# MCU.net
KiCad netlist of a schematic drawn in Altium Designer
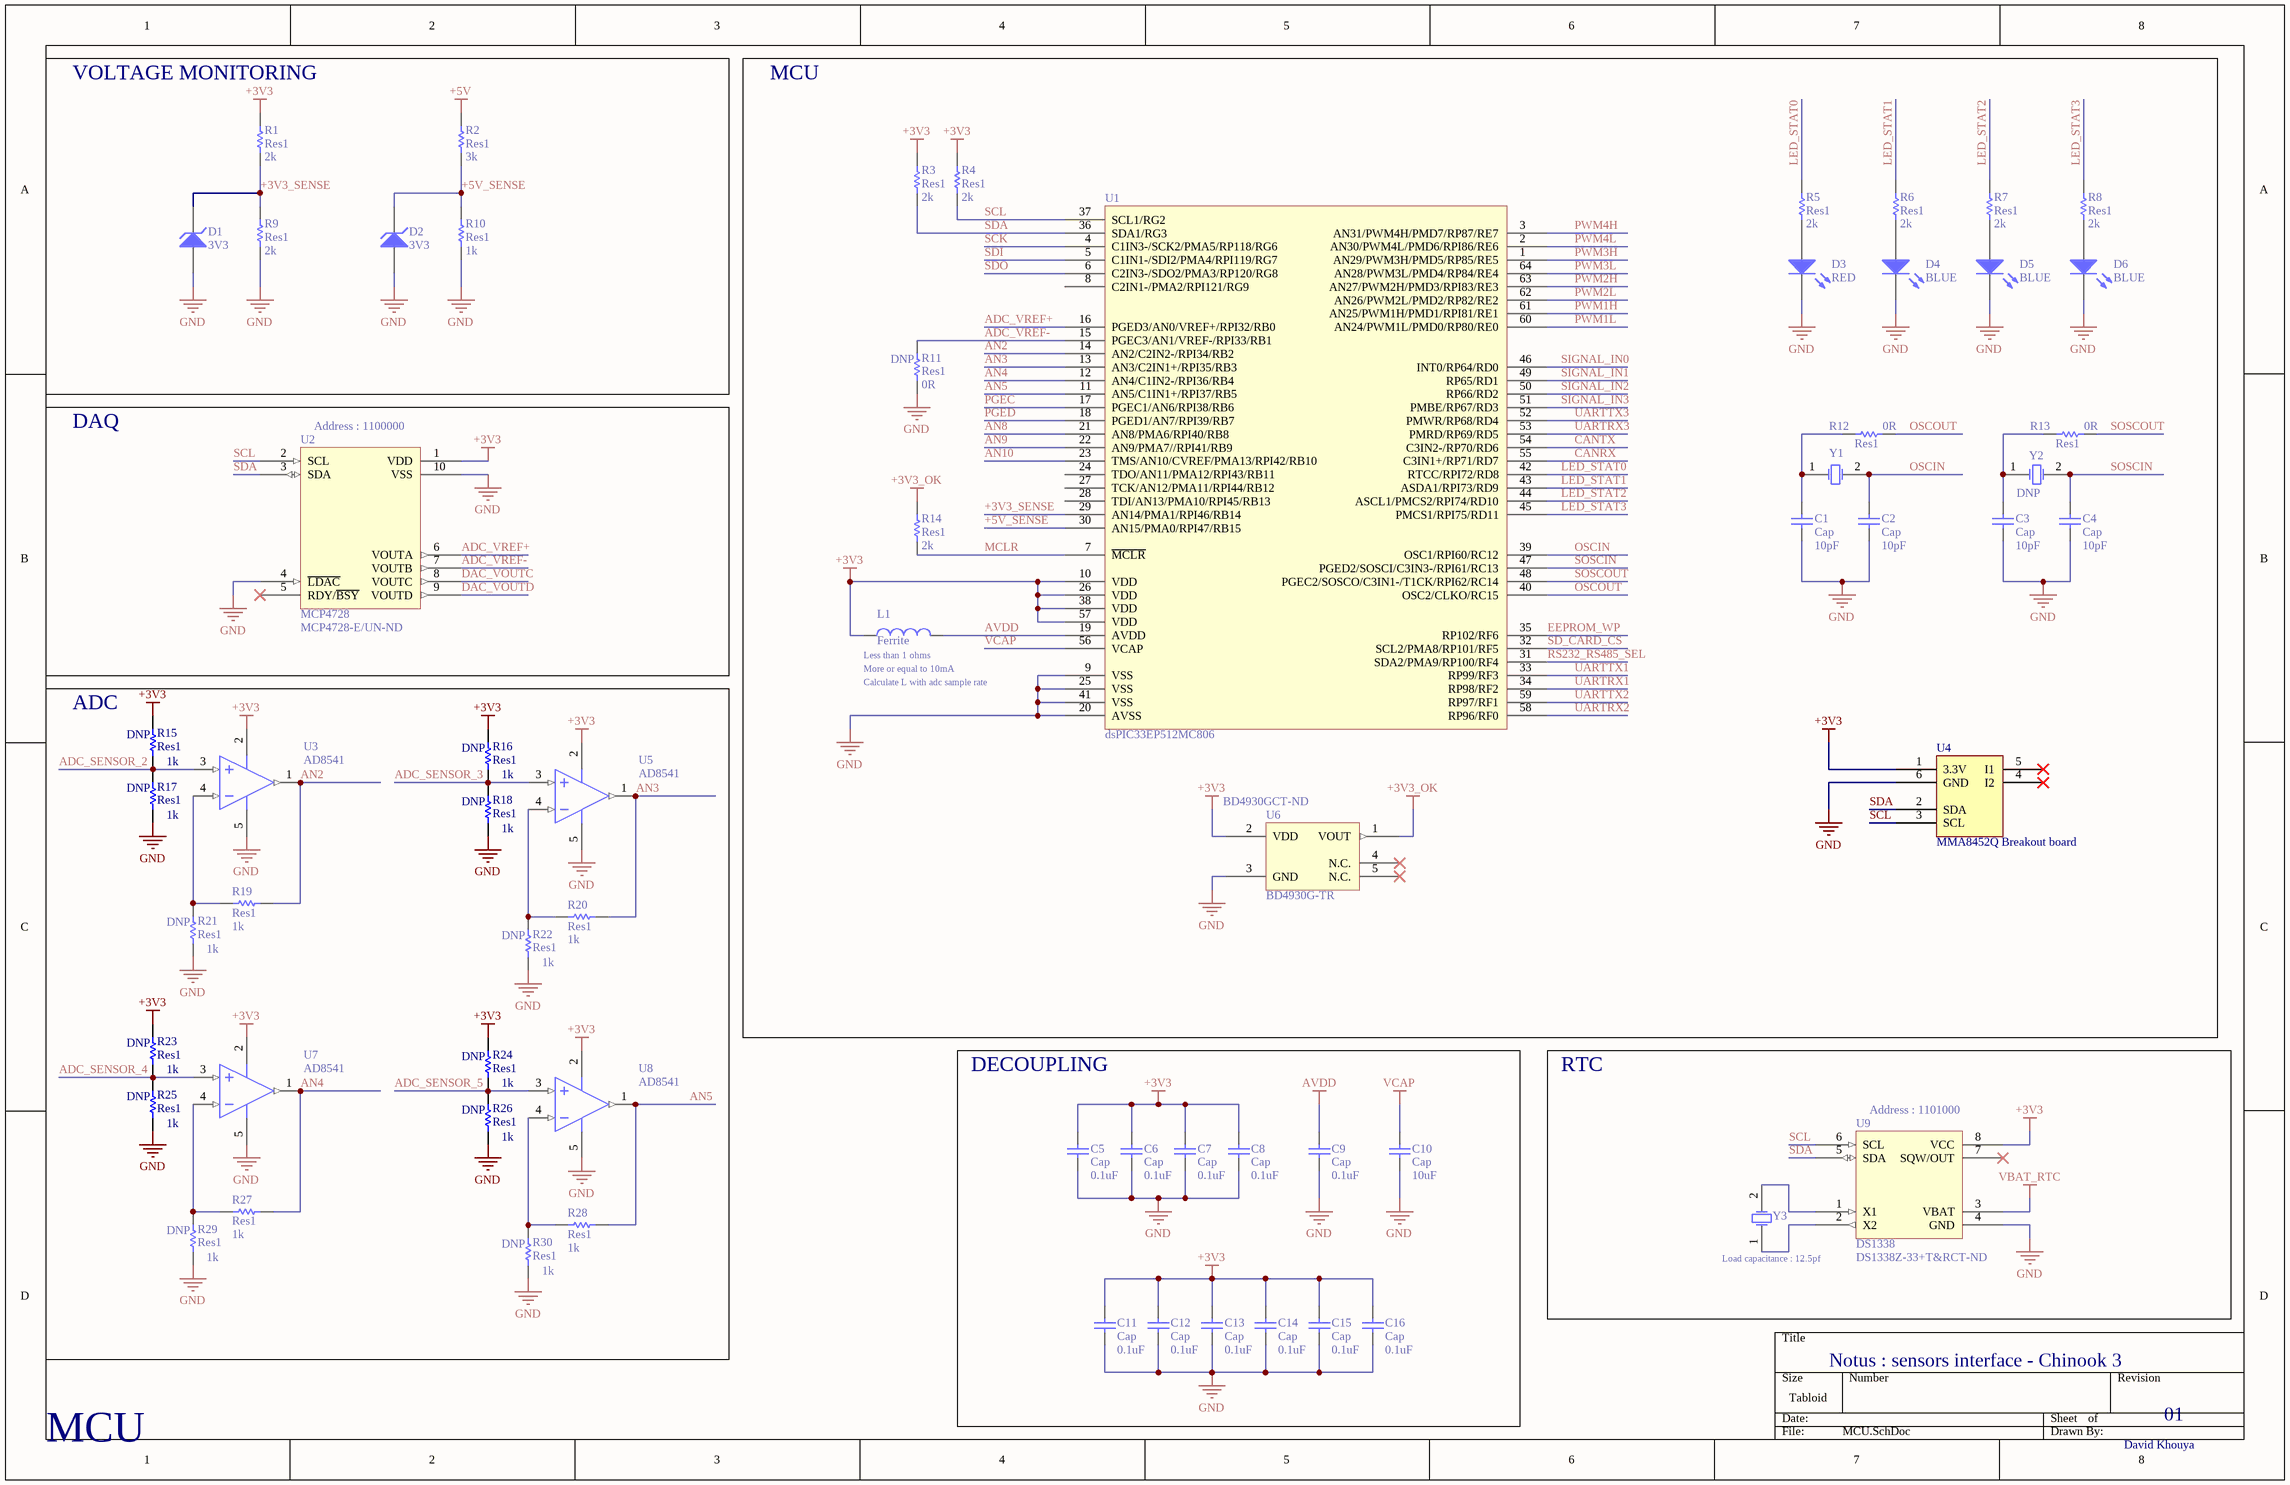
[diagram p0: MCU.SchDoc]

(export (version "E")
  (design (tool "Eeschema 10.0.6"))
  (components
    (comp (ref "C1")
      (value "Cap")
      (footprint "RESC2012N")
      (description "Capacitor")
      (fields (field (name "ALTIUM_VALUE") "10pF") (field (name "PUBLISHER") "Altium Limited"))
      (libsource (lib "Miscellaneous Devices") (part "Cap"))
    )
    (comp (ref "C2")
      (value "Cap")
      (footprint "RESC2012N")
      (description "Capacitor")
      (fields (field (name "ALTIUM_VALUE") "10pF") (field (name "PUBLISHER") "Altium Limited"))
      (libsource (lib "Miscellaneous Devices") (part "Cap"))
    )
    (comp (ref "C3")
      (value "Cap")
      (footprint "RESC2012N")
      (description "Capacitor")
      (fields (field (name "ALTIUM_VALUE") "10pF") (field (name "PUBLISHER") "Altium Limited"))
      (libsource (lib "Miscellaneous Devices") (part "Cap"))
    )
    (comp (ref "C4")
      (value "Cap")
      (footprint "RESC2012N")
      (description "Capacitor")
      (fields (field (name "ALTIUM_VALUE") "10pF") (field (name "PUBLISHER") "Altium Limited"))
      (libsource (lib "Miscellaneous Devices") (part "Cap"))
    )
    (comp (ref "C5")
      (value "Cap")
      (footprint "RESC2012N")
      (description "Capacitor")
      (fields (field (name "ALTIUM_VALUE") "0.1uF") (field (name "PUBLISHER") "Altium Limited"))
      (libsource (lib "Miscellaneous Devices") (part "Cap"))
    )
    (comp (ref "C6")
      (value "Cap")
      (footprint "RESC2012N")
      (description "Capacitor")
      (fields (field (name "ALTIUM_VALUE") "0.1uF") (field (name "PUBLISHER") "Altium Limited"))
      (libsource (lib "Miscellaneous Devices") (part "Cap"))
    )
    (comp (ref "C7")
      (value "Cap")
      (footprint "RESC2012N")
      (description "Capacitor")
      (fields (field (name "ALTIUM_VALUE") "0.1uF") (field (name "PUBLISHER") "Altium Limited"))
      (libsource (lib "Miscellaneous Devices") (part "Cap"))
    )
    (comp (ref "C8")
      (value "Cap")
      (footprint "RESC2012N")
      (description "Capacitor")
      (fields (field (name "ALTIUM_VALUE") "0.1uF") (field (name "PUBLISHER") "Altium Limited"))
      (libsource (lib "Miscellaneous Devices") (part "Cap"))
    )
    (comp (ref "C9")
      (value "Cap")
      (footprint "RESC2012N")
      (description "Capacitor")
      (fields (field (name "ALTIUM_VALUE") "0.1uF") (field (name "PUBLISHER") "Altium Limited"))
      (libsource (lib "Miscellaneous Devices") (part "Cap"))
    )
    (comp (ref "C10")
      (value "Cap")
      (footprint "RESC2012N")
      (description "Capacitor")
      (fields (field (name "ALTIUM_VALUE") "10uF") (field (name "PUBLISHER") "Altium Limited"))
      (libsource (lib "Miscellaneous Devices") (part "Cap"))
    )
    (comp (ref "C11")
      (value "Cap")
      (footprint "RESC2012N")
      (description "Capacitor")
      (fields (field (name "ALTIUM_VALUE") "0.1uF") (field (name "PUBLISHER") "Altium Limited"))
      (libsource (lib "Miscellaneous Devices") (part "Cap"))
    )
    (comp (ref "C12")
      (value "Cap")
      (footprint "RESC2012N")
      (description "Capacitor")
      (fields (field (name "ALTIUM_VALUE") "0.1uF") (field (name "PUBLISHER") "Altium Limited"))
      (libsource (lib "Miscellaneous Devices") (part "Cap"))
    )
    (comp (ref "C13")
      (value "Cap")
      (footprint "RESC2012N")
      (description "Capacitor")
      (fields (field (name "ALTIUM_VALUE") "0.1uF") (field (name "PUBLISHER") "Altium Limited"))
      (libsource (lib "Miscellaneous Devices") (part "Cap"))
    )
    (comp (ref "C14")
      (value "Cap")
      (footprint "RESC2012N")
      (description "Capacitor")
      (fields (field (name "ALTIUM_VALUE") "0.1uF") (field (name "PUBLISHER") "Altium Limited"))
      (libsource (lib "Miscellaneous Devices") (part "Cap"))
    )
    (comp (ref "C15")
      (value "Cap")
      (footprint "RESC2012N")
      (description "Capacitor")
      (fields (field (name "ALTIUM_VALUE") "0.1uF") (field (name "PUBLISHER") "Altium Limited"))
      (libsource (lib "Miscellaneous Devices") (part "Cap"))
    )
    (comp (ref "C16")
      (value "Cap")
      (footprint "RESC2012N")
      (description "Capacitor")
      (fields (field (name "ALTIUM_VALUE") "0.1uF") (field (name "PUBLISHER") "Altium Limited"))
      (libsource (lib "Miscellaneous Devices") (part "Cap"))
    )
    (comp (ref "D1")
      (value "3V3")
      (footprint "SOT23-3M")
      (description "Zener Diode")
      (fields (field (name "PUBLISHER") "Altium Limited"))
      (libsource (lib "Miscellaneous Devices") (part "D Zener"))
    )
    (comp (ref "D2")
      (value "3V3")
      (footprint "SOT23-3M")
      (description "Zener Diode")
      (fields (field (name "PUBLISHER") "Altium Limited"))
      (libsource (lib "Miscellaneous Devices") (part "D Zener"))
    )
    (comp (ref "D3")
      (value "RED")
      (footprint "0805_Diode")
      (description "Typical INFRARED GaAs LED")
      (fields (field (name "PUBLISHER") "Altium Limited"))
      (libsource (lib "Miscellaneous Devices") (part "LED0"))
    )
    (comp (ref "D4")
      (value "BLUE")
      (footprint "0805_Diode")
      (description "Typical INFRARED GaAs LED")
      (fields (field (name "PUBLISHER") "Altium Limited"))
      (libsource (lib "Miscellaneous Devices") (part "LED0"))
    )
    (comp (ref "D5")
      (value "BLUE")
      (footprint "0805_Diode")
      (description "Typical INFRARED GaAs LED")
      (fields (field (name "PUBLISHER") "Altium Limited"))
      (libsource (lib "Miscellaneous Devices") (part "LED0"))
    )
    (comp (ref "D6")
      (value "BLUE")
      (footprint "0805_Diode")
      (description "Typical INFRARED GaAs LED")
      (fields (field (name "PUBLISHER") "Altium Limited"))
      (libsource (lib "Miscellaneous Devices") (part "LED0"))
    )
    (comp (ref "L1")
      (value "Ferrite")
      (footprint "RESC2012N")
      (description "Inductor")
      (fields (field (name "PUBLISHER") "Altium Limited"))
      (libsource (lib "Miscellaneous Devices") (part "Inductor"))
    )
    (comp (ref "R1")
      (value "Res1")
      (footprint "RESC2012N")
      (description "Resistor")
      (fields (field (name "ALTIUM_VALUE") "2k") (field (name "PUBLISHER") "Altium Limited"))
      (libsource (lib "Miscellaneous Devices") (part "Res1"))
    )
    (comp (ref "R2")
      (value "Res1")
      (footprint "RESC2012N")
      (description "Resistor")
      (fields (field (name "ALTIUM_VALUE") "3k") (field (name "PUBLISHER") "Altium Limited"))
      (libsource (lib "Miscellaneous Devices") (part "Res1"))
    )
    (comp (ref "R3")
      (value "Res1")
      (footprint "RESC2012N")
      (description "Resistor")
      (fields (field (name "ALTIUM_VALUE") "2k") (field (name "PUBLISHER") "Altium Limited"))
      (libsource (lib "Miscellaneous Devices") (part "Res1"))
    )
    (comp (ref "R4")
      (value "Res1")
      (footprint "RESC2012N")
      (description "Resistor")
      (fields (field (name "ALTIUM_VALUE") "2k") (field (name "PUBLISHER") "Altium Limited"))
      (libsource (lib "Miscellaneous Devices") (part "Res1"))
    )
    (comp (ref "R5")
      (value "Res1")
      (footprint "RESC2012N")
      (description "Resistor")
      (fields (field (name "ALTIUM_VALUE") "2k") (field (name "PUBLISHER") "Altium Limited"))
      (libsource (lib "Miscellaneous Devices") (part "Res1"))
    )
    (comp (ref "R6")
      (value "Res1")
      (footprint "RESC2012N")
      (description "Resistor")
      (fields (field (name "ALTIUM_VALUE") "2k") (field (name "PUBLISHER") "Altium Limited"))
      (libsource (lib "Miscellaneous Devices") (part "Res1"))
    )
    (comp (ref "R7")
      (value "Res1")
      (footprint "RESC2012N")
      (description "Resistor")
      (fields (field (name "ALTIUM_VALUE") "2k") (field (name "PUBLISHER") "Altium Limited"))
      (libsource (lib "Miscellaneous Devices") (part "Res1"))
    )
    (comp (ref "R8")
      (value "Res1")
      (footprint "RESC2012N")
      (description "Resistor")
      (fields (field (name "ALTIUM_VALUE") "2k") (field (name "PUBLISHER") "Altium Limited"))
      (libsource (lib "Miscellaneous Devices") (part "Res1"))
    )
    (comp (ref "R9")
      (value "Res1")
      (footprint "RESC2012N")
      (description "Resistor")
      (fields (field (name "ALTIUM_VALUE") "2k") (field (name "PUBLISHER") "Altium Limited"))
      (libsource (lib "Miscellaneous Devices") (part "Res1"))
    )
    (comp (ref "R10")
      (value "Res1")
      (footprint "RESC2012N")
      (description "Resistor")
      (fields (field (name "ALTIUM_VALUE") "1k") (field (name "PUBLISHER") "Altium Limited"))
      (libsource (lib "Miscellaneous Devices") (part "Res1"))
    )
    (comp (ref "R11")
      (value "Res1")
      (footprint "RESC2012N")
      (description "Resistor")
      (fields
        (field (name "ALTIUM_VALUE") "0R")
        (field (name "DNP") "DNP")
        (field (name "PUBLISHER") "Altium Limited")
      )
      (libsource (lib "Miscellaneous Devices") (part "Res1"))
    )
    (comp (ref "R12")
      (value "Res1")
      (footprint "RESC2012N")
      (description "Resistor")
      (fields (field (name "ALTIUM_VALUE") "0R") (field (name "PUBLISHER") "Altium Limited"))
      (libsource (lib "Miscellaneous Devices") (part "Res1"))
    )
    (comp (ref "R13")
      (value "Res1")
      (footprint "RESC2012N")
      (description "Resistor")
      (fields (field (name "ALTIUM_VALUE") "0R") (field (name "PUBLISHER") "Altium Limited"))
      (libsource (lib "Miscellaneous Devices") (part "Res1"))
    )
    (comp (ref "R14")
      (value "Res1")
      (footprint "RESC2012N")
      (description "Resistor")
      (fields (field (name "ALTIUM_VALUE") "2k") (field (name "PUBLISHER") "Altium Limited"))
      (libsource (lib "Miscellaneous Devices") (part "Res1"))
    )
    (comp (ref "R15")
      (value "Res1")
      (footprint "RESC2012N")
      (description "Resistor")
      (fields
        (field (name "ALTIUM_VALUE") "1k")
        (field (name "DNP") "DNP")
        (field (name "PUBLISHER") "Altium Limited")
      )
      (libsource (lib "Miscellaneous Devices") (part "Res1"))
    )
    (comp (ref "R16")
      (value "Res1")
      (footprint "RESC2012N")
      (description "Resistor")
      (fields
        (field (name "ALTIUM_VALUE") "1k")
        (field (name "DNP") "DNP")
        (field (name "PUBLISHER") "Altium Limited")
      )
      (libsource (lib "Miscellaneous Devices") (part "Res1"))
    )
    (comp (ref "R17")
      (value "Res1")
      (footprint "RESC2012N")
      (description "Resistor")
      (fields
        (field (name "ALTIUM_VALUE") "1k")
        (field (name "DNP") "DNP")
        (field (name "PUBLISHER") "Altium Limited")
      )
      (libsource (lib "Miscellaneous Devices") (part "Res1"))
    )
    (comp (ref "R18")
      (value "Res1")
      (footprint "RESC2012N")
      (description "Resistor")
      (fields
        (field (name "ALTIUM_VALUE") "1k")
        (field (name "DNP") "DNP")
        (field (name "PUBLISHER") "Altium Limited")
      )
      (libsource (lib "Miscellaneous Devices") (part "Res1"))
    )
    (comp (ref "R19")
      (value "Res1")
      (footprint "RESC2012N")
      (description "Resistor")
      (fields (field (name "ALTIUM_VALUE") "1k") (field (name "PUBLISHER") "Altium Limited"))
      (libsource (lib "Miscellaneous Devices") (part "Res1"))
    )
    (comp (ref "R20")
      (value "Res1")
      (footprint "RESC2012N")
      (description "Resistor")
      (fields (field (name "ALTIUM_VALUE") "1k") (field (name "PUBLISHER") "Altium Limited"))
      (libsource (lib "Miscellaneous Devices") (part "Res1"))
    )
    (comp (ref "R21")
      (value "Res1")
      (footprint "RESC2012N")
      (description "Resistor")
      (fields
        (field (name "ALTIUM_VALUE") "1k")
        (field (name "DNP") "DNP")
        (field (name "PUBLISHER") "Altium Limited")
      )
      (libsource (lib "Miscellaneous Devices") (part "Res1"))
    )
    (comp (ref "R22")
      (value "Res1")
      (footprint "RESC2012N")
      (description "Resistor")
      (fields
        (field (name "ALTIUM_VALUE") "1k")
        (field (name "DNP") "DNP")
        (field (name "PUBLISHER") "Altium Limited")
      )
      (libsource (lib "Miscellaneous Devices") (part "Res1"))
    )
    (comp (ref "R23")
      (value "Res1")
      (footprint "RESC2012N")
      (description "Resistor")
      (fields
        (field (name "ALTIUM_VALUE") "1k")
        (field (name "DNP") "DNP")
        (field (name "PUBLISHER") "Altium Limited")
      )
      (libsource (lib "Miscellaneous Devices") (part "Res1"))
    )
    (comp (ref "R24")
      (value "Res1")
      (footprint "RESC2012N")
      (description "Resistor")
      (fields
        (field (name "ALTIUM_VALUE") "1k")
        (field (name "DNP") "DNP")
        (field (name "PUBLISHER") "Altium Limited")
      )
      (libsource (lib "Miscellaneous Devices") (part "Res1"))
    )
    (comp (ref "R25")
      (value "Res1")
      (footprint "RESC2012N")
      (description "Resistor")
      (fields
        (field (name "ALTIUM_VALUE") "1k")
        (field (name "DNP") "DNP")
        (field (name "PUBLISHER") "Altium Limited")
      )
      (libsource (lib "Miscellaneous Devices") (part "Res1"))
    )
    (comp (ref "R26")
      (value "Res1")
      (footprint "RESC2012N")
      (description "Resistor")
      (fields
        (field (name "ALTIUM_VALUE") "1k")
        (field (name "DNP") "DNP")
        (field (name "PUBLISHER") "Altium Limited")
      )
      (libsource (lib "Miscellaneous Devices") (part "Res1"))
    )
    (comp (ref "R27")
      (value "Res1")
      (footprint "RESC2012N")
      (description "Resistor")
      (fields (field (name "ALTIUM_VALUE") "1k") (field (name "PUBLISHER") "Altium Limited"))
      (libsource (lib "Miscellaneous Devices") (part "Res1"))
    )
    (comp (ref "R28")
      (value "Res1")
      (footprint "RESC2012N")
      (description "Resistor")
      (fields (field (name "ALTIUM_VALUE") "1k") (field (name "PUBLISHER") "Altium Limited"))
      (libsource (lib "Miscellaneous Devices") (part "Res1"))
    )
    (comp (ref "R29")
      (value "Res1")
      (footprint "RESC2012N")
      (description "Resistor")
      (fields
        (field (name "ALTIUM_VALUE") "1k")
        (field (name "DNP") "DNP")
        (field (name "PUBLISHER") "Altium Limited")
      )
      (libsource (lib "Miscellaneous Devices") (part "Res1"))
    )
    (comp (ref "R30")
      (value "Res1")
      (footprint "RESC2012N")
      (description "Resistor")
      (fields
        (field (name "ALTIUM_VALUE") "1k")
        (field (name "DNP") "DNP")
        (field (name "PUBLISHER") "Altium Limited")
      )
      (libsource (lib "Miscellaneous Devices") (part "Res1"))
    )
    (comp (ref "U1")
      (value "dsPIC33EP512MC806")
      (footprint "TQFP-PT64_M")
      (description "16 bits microcontroller with Digital signal controller")
      (libsource (lib "dkhouya") (part "dsPIC33EP512MC806"))
    )
    (comp (ref "U2")
      (value "MCP4728")
      (description "12-Bit, Quad Digital-to-Analog Converter with EEPROM Memory")
      (fields (field (name "SUPPLIER PART NUMBER 1") "MCP4728-E/UN-ND"))
      (libsource (lib "dkhouya") (part "MCP4728"))
    )
    (comp (ref "U3")
      (value "AD8541")
      (footprint "RT-5")
      (description "CMOS Rail-to-Rail General-Purpose Amplifiers")
      (libsource (lib "dkhouya") (part "AD8541"))
    )
    (comp (ref "U4")
      (value "MMA8452Q Breakout board")
      (footprint "MMA8452Q Breakout board")
      (description "Triple axis accelerometer breakout board")
      (libsource (lib "dkhouya") (part "MMA8452Q Breakout board"))
    )
    (comp (ref "U5")
      (value "AD8541")
      (footprint "RT-5")
      (description "CMOS Rail-to-Rail General-Purpose Amplifiers")
      (libsource (lib "dkhouya") (part "AD8541"))
    )
    (comp (ref "U6")
      (value "BD4930G-TR")
      (footprint "SSOP5")
      (description "5V Voltage supervisor")
      (fields (field (name "SUPPLIER PART NUMBER 1") "BD4930GCT-ND"))
      (libsource (lib "dkhouya") (part "BD4950G-TR"))
    )
    (comp (ref "U7")
      (value "AD8541")
      (footprint "RT-5")
      (description "CMOS Rail-to-Rail General-Purpose Amplifiers")
      (libsource (lib "dkhouya") (part "AD8541"))
    )
    (comp (ref "U8")
      (value "AD8541")
      (footprint "RT-5")
      (description "CMOS Rail-to-Rail General-Purpose Amplifiers")
      (libsource (lib "dkhouya") (part "AD8541"))
    )
    (comp (ref "U9")
      (value "DS1338")
      (footprint "8SOIC-1")
      (description "I2C RTC with 56-Byte NV RAM")
      (fields (field (name "SUPPLIER PART NUMBER 1") "DS1338Z-33+T&RCT-ND"))
      (libsource (lib "dkhouya") (part "DS1338"))
    )
    (comp (ref "Y1")
      (value "~")
      (footprint "HC49/4H_SMX")
      (description "Crystal Oscillator")
      (fields (field (name "PUBLISHER") "Altium Limited"))
      (libsource (lib "Miscellaneous Devices") (part "XTAL"))
    )
    (comp (ref "Y2")
      (value "~")
      (footprint "HC49/4H_SMX")
      (description "Crystal Oscillator")
      (fields (field (name "DNP") "DNP") (field (name "PUBLISHER") "Altium Limited"))
      (libsource (lib "Miscellaneous Devices") (part "XTAL"))
    )
    (comp (ref "Y3")
      (value "~")
      (footprint "HC49/4H_SMX")
      (description "Crystal Oscillator")
      (fields (field (name "PUBLISHER") "Altium Limited"))
      (libsource (lib "Miscellaneous Devices") (part "XTAL"))
    )
  )
  (nets
    (net (code "1") (name "+3V3") (class "Default")
      (node (ref "C11") (pin "2") (pinfunction "2_2") (pintype "passive"))
      (node (ref "C12") (pin "2") (pinfunction "2_2") (pintype "passive"))
      (node (ref "C13") (pin "2") (pinfunction "2_2") (pintype "passive"))
      (node (ref "C14") (pin "2") (pinfunction "2_2") (pintype "passive"))
      (node (ref "C15") (pin "2") (pinfunction "2_2") (pintype "passive"))
      (node (ref "C16") (pin "2") (pinfunction "2_2") (pintype "passive"))
      (node (ref "C5") (pin "2") (pinfunction "2_2") (pintype "passive"))
      (node (ref "C6") (pin "2") (pinfunction "2_2") (pintype "passive"))
      (node (ref "C7") (pin "2") (pinfunction "2_2") (pintype "passive"))
      (node (ref "C8") (pin "2") (pinfunction "2_2") (pintype "passive"))
      (node (ref "L1") (pin "1") (pinfunction "1_1") (pintype "passive"))
      (node (ref "R1") (pin "1") (pinfunction "1_1") (pintype "passive"))
      (node (ref "R15") (pin "1") (pinfunction "1_1") (pintype "passive"))
      (node (ref "R16") (pin "1") (pinfunction "1_1") (pintype "passive"))
      (node (ref "R23") (pin "1") (pinfunction "1_1") (pintype "passive"))
      (node (ref "R24") (pin "1") (pinfunction "1_1") (pintype "passive"))
      (node (ref "R3") (pin "1") (pinfunction "1_1") (pintype "passive"))
      (node (ref "R4") (pin "1") (pinfunction "1_1") (pintype "passive"))
      (node (ref "U1") (pin "10") (pinfunction "VDD_10") (pintype "passive"))
      (node (ref "U1") (pin "26") (pinfunction "VDD_26") (pintype "passive"))
      (node (ref "U1") (pin "38") (pinfunction "VDD_38") (pintype "passive"))
      (node (ref "U1") (pin "57") (pinfunction "VDD_57") (pintype "passive"))
      (node (ref "U2") (pin "1") (pinfunction "VDD_1") (pintype "power_in"))
      (node (ref "U3") (pin "2") (pinfunction "V-_2") (pintype "power_in"))
      (node (ref "U4") (pin "1") (pinfunction "3.3V_1") (pintype "passive"))
      (node (ref "U5") (pin "2") (pinfunction "V-_2") (pintype "power_in"))
      (node (ref "U6") (pin "2") (pinfunction "VDD_2") (pintype "power_in"))
      (node (ref "U7") (pin "2") (pinfunction "V-_2") (pintype "power_in"))
      (node (ref "U8") (pin "2") (pinfunction "V-_2") (pintype "power_in"))
      (node (ref "U9") (pin "8") (pinfunction "VCC_8") (pintype "power_in"))
    )
    (net (code "2") (name "+3V3_OK") (class "Default")
      (node (ref "R14") (pin "1") (pinfunction "1_1") (pintype "passive"))
      (node (ref "U6") (pin "1") (pinfunction "VOUT_1") (pintype "output"))
    )
    (net (code "3") (name "+5V") (class "Default")
      (node (ref "R2") (pin "1") (pinfunction "1_1") (pintype "passive"))
    )
    (net (code "4") (name "/+3V3_SENSE") (class "Default")
      (node (ref "D1") (pin "2") (pinfunction "K_2") (pintype "passive"))
      (node (ref "R1") (pin "2") (pinfunction "2_2") (pintype "passive"))
      (node (ref "R9") (pin "1") (pinfunction "1_1") (pintype "passive"))
      (node (ref "U1") (pin "29") (pinfunction "AN14/PMA1/RPI46/RB14_29") (pintype "passive"))
    )
    (net (code "5") (name "/+5V_SENSE") (class "Default")
      (node (ref "D2") (pin "2") (pinfunction "K_2") (pintype "passive"))
      (node (ref "R10") (pin "1") (pinfunction "1_1") (pintype "passive"))
      (node (ref "R2") (pin "2") (pinfunction "2_2") (pintype "passive"))
      (node (ref "U1") (pin "30") (pinfunction "AN15/PMA0/RPI47/RB15_30") (pintype "passive"))
    )
    (net (code "6") (name "/ADC_SENSOR_2") (class "Default")
      (node (ref "R15") (pin "2") (pinfunction "2_2") (pintype "passive"))
      (node (ref "R17") (pin "1") (pinfunction "1_1") (pintype "passive"))
      (node (ref "U3") (pin "3") (pinfunction "IN+_A_3") (pintype "input"))
    )
    (net (code "7") (name "/ADC_SENSOR_3") (class "Default")
      (node (ref "R16") (pin "2") (pinfunction "2_2") (pintype "passive"))
      (node (ref "R18") (pin "1") (pinfunction "1_1") (pintype "passive"))
      (node (ref "U5") (pin "3") (pinfunction "IN+_A_3") (pintype "input"))
    )
    (net (code "8") (name "/ADC_SENSOR_4") (class "Default")
      (node (ref "R23") (pin "2") (pinfunction "2_2") (pintype "passive"))
      (node (ref "R25") (pin "1") (pinfunction "1_1") (pintype "passive"))
      (node (ref "U7") (pin "3") (pinfunction "IN+_A_3") (pintype "input"))
    )
    (net (code "9") (name "/ADC_SENSOR_5") (class "Default")
      (node (ref "R24") (pin "2") (pinfunction "2_2") (pintype "passive"))
      (node (ref "R26") (pin "1") (pinfunction "1_1") (pintype "passive"))
      (node (ref "U8") (pin "3") (pinfunction "IN+_A_3") (pintype "input"))
    )
    (net (code "10") (name "/ADC_VREF+") (class "Default")
      (node (ref "U1") (pin "16") (pinfunction "PGED3/AN0/VREF+/RPI32/RB0_16") (pintype "passive"))
      (node (ref "U2") (pin "6") (pinfunction "VOUTA_6") (pintype "output"))
    )
    (net (code "11") (name "/ADC_VREF-") (class "Default")
      (node (ref "R11") (pin "1") (pinfunction "1_1") (pintype "passive"))
      (node (ref "U1") (pin "15") (pinfunction "PGEC3/AN1/VREF-/RPI33/RB1_15") (pintype "passive"))
      (node (ref "U2") (pin "7") (pinfunction "VOUTB_7") (pintype "output"))
    )
    (net (code "12") (name "/AN2") (class "Default")
      (node (ref "R19") (pin "2") (pinfunction "2_2") (pintype "passive"))
      (node (ref "U1") (pin "14") (pinfunction "AN2/C2IN2-/RPI34/RB2_14") (pintype "passive"))
      (node (ref "U3") (pin "1") (pinfunction "OUT_A_1") (pintype "output"))
    )
    (net (code "13") (name "/AN3") (class "Default")
      (node (ref "R20") (pin "2") (pinfunction "2_2") (pintype "passive"))
      (node (ref "U1") (pin "13") (pinfunction "AN3/C2IN1+/RPI35/RB3_13") (pintype "passive"))
      (node (ref "U5") (pin "1") (pinfunction "OUT_A_1") (pintype "output"))
    )
    (net (code "14") (name "/AN4") (class "Default")
      (node (ref "R27") (pin "2") (pinfunction "2_2") (pintype "passive"))
      (node (ref "U1") (pin "12") (pinfunction "AN4/C1IN2-/RPI36/RB4_12") (pintype "passive"))
      (node (ref "U7") (pin "1") (pinfunction "OUT_A_1") (pintype "output"))
    )
    (net (code "15") (name "/AN5") (class "Default")
      (node (ref "R28") (pin "2") (pinfunction "2_2") (pintype "passive"))
      (node (ref "U1") (pin "11") (pinfunction "AN5/C1IN1+/RPI37/RB5_11") (pintype "passive"))
      (node (ref "U8") (pin "1") (pinfunction "OUT_A_1") (pintype "output"))
    )
    (net (code "16") (name "/AN8") (class "Default")
      (node (ref "U1") (pin "21") (pinfunction "AN8/PMA6/RPI40/RB8_21") (pintype "passive"))
    )
    (net (code "17") (name "/AN9") (class "Default")
      (node (ref "U1") (pin "22") (pinfunction "AN9/PMA7//RPI41/RB9_22") (pintype "passive"))
    )
    (net (code "18") (name "/AN10") (class "Default")
      (node (ref "U1") (pin "23") (pinfunction "TMS/AN10/CVREF/PMA13/RPI42/RB10_23") (pintype "passive"))
    )
    (net (code "19") (name "/CANRX") (class "Default")
      (node (ref "U1") (pin "55") (pinfunction "C3IN1+/RP71/RD7_55") (pintype "passive"))
    )
    (net (code "20") (name "/CANTX") (class "Default")
      (node (ref "U1") (pin "54") (pinfunction "C3IN2-/RP70/RD6_54") (pintype "passive"))
    )
    (net (code "21") (name "/DAC_VOUTC") (class "Default")
      (node (ref "U2") (pin "8") (pinfunction "VOUTC_8") (pintype "output"))
    )
    (net (code "22") (name "/DAC_VOUTD") (class "Default")
      (node (ref "U2") (pin "9") (pinfunction "VOUTD_9") (pintype "output"))
    )
    (net (code "23") (name "/EEPROM_WP") (class "Default")
      (node (ref "U1") (pin "35") (pinfunction "RP102/RF6_35") (pintype "passive"))
    )
    (net (code "24") (name "/LED_STAT0") (class "Default")
      (node (ref "R5") (pin "1") (pinfunction "1_1") (pintype "passive"))
      (node (ref "U1") (pin "42") (pinfunction "RTCC/RPI72/RD8_42") (pintype "passive"))
    )
    (net (code "25") (name "/LED_STAT1") (class "Default")
      (node (ref "R6") (pin "1") (pinfunction "1_1") (pintype "passive"))
      (node (ref "U1") (pin "43") (pinfunction "ASDA1/RPI73/RD9_43") (pintype "passive"))
    )
    (net (code "26") (name "/LED_STAT2") (class "Default")
      (node (ref "R7") (pin "1") (pinfunction "1_1") (pintype "passive"))
      (node (ref "U1") (pin "44") (pinfunction "ASCL1/PMCS2/RPI74/RD10_44") (pintype "passive"))
    )
    (net (code "27") (name "/LED_STAT3") (class "Default")
      (node (ref "R8") (pin "1") (pinfunction "1_1") (pintype "passive"))
      (node (ref "U1") (pin "45") (pinfunction "PMCS1/RPI75/RD11_45") (pintype "passive"))
    )
    (net (code "28") (name "/MCLR") (class "Default")
      (node (ref "R14") (pin "2") (pinfunction "2_2") (pintype "passive"))
      (node (ref "U1") (pin "7") (pinfunction "~{MCLR}_7") (pintype "passive"))
    )
    (net (code "29") (name "/OSCIN") (class "Default")
      (node (ref "C2") (pin "2") (pinfunction "2_2") (pintype "passive"))
      (node (ref "U1") (pin "39") (pinfunction "OSC1/RPI60/RC12_39") (pintype "passive"))
      (node (ref "Y1") (pin "2") (pinfunction "OSC2_2") (pintype "passive"))
    )
    (net (code "30") (name "/OSCOUT") (class "Default")
      (node (ref "R12") (pin "1") (pinfunction "1_1") (pintype "passive"))
      (node (ref "U1") (pin "40") (pinfunction "OSC2/CLKO/RC15_40") (pintype "passive"))
    )
    (net (code "31") (name "/PGEC") (class "Default")
      (node (ref "U1") (pin "17") (pinfunction "PGEC1/AN6/RPI38/RB6_17") (pintype "passive"))
    )
    (net (code "32") (name "/PGED") (class "Default")
      (node (ref "U1") (pin "18") (pinfunction "PGED1/AN7/RPI39/RB7_18") (pintype "passive"))
    )
    (net (code "33") (name "/PWM1H") (class "Default")
      (node (ref "U1") (pin "61") (pinfunction "AN25/PWM1H/PMD1/RPI81/RE1_61") (pintype "passive"))
    )
    (net (code "34") (name "/PWM1L") (class "Default")
      (node (ref "U1") (pin "60") (pinfunction "AN24/PWM1L/PMD0/RP80/RE0_60") (pintype "passive"))
    )
    (net (code "35") (name "/PWM2H") (class "Default")
      (node (ref "U1") (pin "63") (pinfunction "AN27/PWM2H/PMD3/RPI83/RE3_63") (pintype "passive"))
    )
    (net (code "36") (name "/PWM2L") (class "Default")
      (node (ref "U1") (pin "62") (pinfunction "AN26/PWM2L/PMD2/RP82/RE2_62") (pintype "passive"))
    )
    (net (code "37") (name "/PWM3H") (class "Default")
      (node (ref "U1") (pin "1") (pinfunction "AN29/PWM3H/PMD5/RP85/RE5_1") (pintype "passive"))
    )
    (net (code "38") (name "/PWM3L") (class "Default")
      (node (ref "U1") (pin "64") (pinfunction "AN28/PWM3L/PMD4/RP84/RE4_64") (pintype "passive"))
    )
    (net (code "39") (name "/PWM4H") (class "Default")
      (node (ref "U1") (pin "3") (pinfunction "AN31/PWM4H/PMD7/RP87/RE7_3") (pintype "passive"))
    )
    (net (code "40") (name "/PWM4L") (class "Default")
      (node (ref "U1") (pin "2") (pinfunction "AN30/PWM4L/PMD6/RPI86/RE6_2") (pintype "passive"))
    )
    (net (code "41") (name "/RS232_RS485_SEL") (class "Default")
      (node (ref "U1") (pin "31") (pinfunction "SDA2/PMA9/RP100/RF4_31") (pintype "passive"))
    )
    (net (code "42") (name "/SCK") (class "Default")
      (node (ref "U1") (pin "4") (pinfunction "C1IN3-/SCK2/PMA5/RP118/RG6_4") (pintype "passive"))
    )
    (net (code "43") (name "/SCL") (class "Default")
      (node (ref "R4") (pin "2") (pinfunction "2_2") (pintype "passive"))
      (node (ref "U1") (pin "37") (pinfunction "SCL1/RG2_37") (pintype "passive"))
      (node (ref "U2") (pin "2") (pinfunction "SCL_2") (pintype "input"))
      (node (ref "U4") (pin "3") (pinfunction "SCL_3") (pintype "passive"))
      (node (ref "U9") (pin "6") (pinfunction "SCL_6") (pintype "input"))
    )
    (net (code "44") (name "/SDA") (class "Default")
      (node (ref "R3") (pin "2") (pinfunction "2_2") (pintype "passive"))
      (node (ref "U1") (pin "36") (pinfunction "SDA1/RG3_36") (pintype "passive"))
      (node (ref "U2") (pin "3") (pinfunction "SDA_3") (pintype "bidirectional"))
      (node (ref "U4") (pin "2") (pinfunction "SDA_2") (pintype "passive"))
      (node (ref "U9") (pin "5") (pinfunction "SDA_5") (pintype "bidirectional"))
    )
    (net (code "45") (name "/SDI") (class "Default")
      (node (ref "U1") (pin "5") (pinfunction "C1IN1-/SDI2/PMA4/RPI119/RG7_5") (pintype "passive"))
    )
    (net (code "46") (name "/SDO") (class "Default")
      (node (ref "U1") (pin "6") (pinfunction "C2IN3-/SDO2/PMA3/RP120/RG8_6") (pintype "passive"))
    )
    (net (code "47") (name "/SD_CARD_CS") (class "Default")
      (node (ref "U1") (pin "32") (pinfunction "SCL2/PMA8/RP101/RF5_32") (pintype "passive"))
    )
    (net (code "48") (name "/SIGNAL_IN0") (class "Default")
      (node (ref "U1") (pin "46") (pinfunction "INT0/RP64/RD0_46") (pintype "passive"))
    )
    (net (code "49") (name "/SIGNAL_IN1") (class "Default")
      (node (ref "U1") (pin "49") (pinfunction "RP65/RD1_49") (pintype "passive"))
    )
    (net (code "50") (name "/SIGNAL_IN2") (class "Default")
      (node (ref "U1") (pin "50") (pinfunction "RP66/RD2_50") (pintype "passive"))
    )
    (net (code "51") (name "/SIGNAL_IN3") (class "Default")
      (node (ref "U1") (pin "51") (pinfunction "PMBE/RP67/RD3_51") (pintype "passive"))
    )
    (net (code "52") (name "/SOSCIN") (class "Default")
      (node (ref "C4") (pin "2") (pinfunction "2_2") (pintype "passive"))
      (node (ref "U1") (pin "47") (pinfunction "PGED2/SOSCI/C3IN3-/RPI61/RC13_47") (pintype "passive"))
      (node (ref "Y2") (pin "2") (pinfunction "OSC2_2") (pintype "passive"))
    )
    (net (code "53") (name "/SOSCOUT") (class "Default")
      (node (ref "R13") (pin "1") (pinfunction "1_1") (pintype "passive"))
      (node (ref "U1") (pin "48") (pinfunction "PGEC2/SOSCO/C3IN1-/T1CK/RPI62/RC14_48") (pintype "passive"))
    )
    (net (code "54") (name "/UARTRX1") (class "Default")
      (node (ref "U1") (pin "34") (pinfunction "RP98/RF2_34") (pintype "passive"))
    )
    (net (code "55") (name "/UARTRX2") (class "Default")
      (node (ref "U1") (pin "58") (pinfunction "RP96/RF0_58") (pintype "passive"))
    )
    (net (code "56") (name "/UARTRX3") (class "Default")
      (node (ref "U1") (pin "53") (pinfunction "PMRD/RP69/RD5_53") (pintype "passive"))
    )
    (net (code "57") (name "/UARTTX1") (class "Default")
      (node (ref "U1") (pin "33") (pinfunction "RP99/RF3_33") (pintype "passive"))
    )
    (net (code "58") (name "/UARTTX2") (class "Default")
      (node (ref "U1") (pin "59") (pinfunction "RP97/RF1_59") (pintype "passive"))
    )
    (net (code "59") (name "/UARTTX3") (class "Default")
      (node (ref "U1") (pin "52") (pinfunction "PMWR/RP68/RD4_52") (pintype "passive"))
    )
    (net (code "60") (name "AVDD") (class "Default")
      (node (ref "C9") (pin "2") (pinfunction "2_2") (pintype "passive"))
      (node (ref "L1") (pin "2") (pinfunction "2_2") (pintype "passive"))
      (node (ref "U1") (pin "19") (pinfunction "AVDD_19") (pintype "passive"))
    )
    (net (code "61") (name "GND") (class "Default")
      (node (ref "C1") (pin "1") (pinfunction "1_1") (pintype "passive"))
      (node (ref "C10") (pin "1") (pinfunction "1_1") (pintype "passive"))
      (node (ref "C11") (pin "1") (pinfunction "1_1") (pintype "passive"))
      (node (ref "C12") (pin "1") (pinfunction "1_1") (pintype "passive"))
      (node (ref "C13") (pin "1") (pinfunction "1_1") (pintype "passive"))
      (node (ref "C14") (pin "1") (pinfunction "1_1") (pintype "passive"))
      (node (ref "C15") (pin "1") (pinfunction "1_1") (pintype "passive"))
      (node (ref "C16") (pin "1") (pinfunction "1_1") (pintype "passive"))
      (node (ref "C2") (pin "1") (pinfunction "1_1") (pintype "passive"))
      (node (ref "C3") (pin "1") (pinfunction "1_1") (pintype "passive"))
      (node (ref "C4") (pin "1") (pinfunction "1_1") (pintype "passive"))
      (node (ref "C5") (pin "1") (pinfunction "1_1") (pintype "passive"))
      (node (ref "C6") (pin "1") (pinfunction "1_1") (pintype "passive"))
      (node (ref "C7") (pin "1") (pinfunction "1_1") (pintype "passive"))
      (node (ref "C8") (pin "1") (pinfunction "1_1") (pintype "passive"))
      (node (ref "C9") (pin "1") (pinfunction "1_1") (pintype "passive"))
      (node (ref "D1") (pin "1") (pinfunction "A_1") (pintype "passive"))
      (node (ref "D2") (pin "1") (pinfunction "A_1") (pintype "passive"))
      (node (ref "D3") (pin "2") (pinfunction "K_2") (pintype "passive"))
      (node (ref "D4") (pin "2") (pinfunction "K_2") (pintype "passive"))
      (node (ref "D5") (pin "2") (pinfunction "K_2") (pintype "passive"))
      (node (ref "D6") (pin "2") (pinfunction "K_2") (pintype "passive"))
      (node (ref "R10") (pin "2") (pinfunction "2_2") (pintype "passive"))
      (node (ref "R11") (pin "2") (pinfunction "2_2") (pintype "passive"))
      (node (ref "R17") (pin "2") (pinfunction "2_2") (pintype "passive"))
      (node (ref "R18") (pin "2") (pinfunction "2_2") (pintype "passive"))
      (node (ref "R21") (pin "2") (pinfunction "2_2") (pintype "passive"))
      (node (ref "R22") (pin "2") (pinfunction "2_2") (pintype "passive"))
      (node (ref "R25") (pin "2") (pinfunction "2_2") (pintype "passive"))
      (node (ref "R26") (pin "2") (pinfunction "2_2") (pintype "passive"))
      (node (ref "R29") (pin "2") (pinfunction "2_2") (pintype "passive"))
      (node (ref "R30") (pin "2") (pinfunction "2_2") (pintype "passive"))
      (node (ref "R9") (pin "2") (pinfunction "2_2") (pintype "passive"))
      (node (ref "U1") (pin "20") (pinfunction "AVSS_20") (pintype "passive"))
      (node (ref "U1") (pin "25") (pinfunction "VSS_25") (pintype "passive"))
      (node (ref "U1") (pin "41") (pinfunction "VSS_41") (pintype "passive"))
      (node (ref "U1") (pin "9") (pinfunction "VSS_9") (pintype "passive"))
      (node (ref "U2") (pin "10") (pinfunction "VSS_10") (pintype "power_in"))
      (node (ref "U2") (pin "4") (pinfunction "~{LDAC}_4") (pintype "input"))
      (node (ref "U3") (pin "5") (pinfunction "V+_5") (pintype "power_in"))
      (node (ref "U4") (pin "6") (pinfunction "GND_6") (pintype "passive"))
      (node (ref "U5") (pin "5") (pinfunction "V+_5") (pintype "power_in"))
      (node (ref "U6") (pin "3") (pinfunction "GND_3") (pintype "passive"))
      (node (ref "U7") (pin "5") (pinfunction "V+_5") (pintype "power_in"))
      (node (ref "U8") (pin "5") (pinfunction "V+_5") (pintype "power_in"))
      (node (ref "U9") (pin "4") (pinfunction "GND_4") (pintype "power_in"))
    )
    (net (code "62") (name "Net-(D3-A)") (class "Default")
      (node (ref "D3") (pin "1") (pinfunction "A_1") (pintype "passive"))
      (node (ref "R5") (pin "2") (pinfunction "2_2") (pintype "passive"))
    )
    (net (code "63") (name "Net-(D4-A)") (class "Default")
      (node (ref "D4") (pin "1") (pinfunction "A_1") (pintype "passive"))
      (node (ref "R6") (pin "2") (pinfunction "2_2") (pintype "passive"))
    )
    (net (code "64") (name "Net-(D5-A)") (class "Default")
      (node (ref "D5") (pin "1") (pinfunction "A_1") (pintype "passive"))
      (node (ref "R7") (pin "2") (pinfunction "2_2") (pintype "passive"))
    )
    (net (code "65") (name "Net-(D6-A)") (class "Default")
      (node (ref "D6") (pin "1") (pinfunction "A_1") (pintype "passive"))
      (node (ref "R8") (pin "2") (pinfunction "2_2") (pintype "passive"))
    )
    (net (code "66") (name "Net-(U3-IN-_A)") (class "Default")
      (node (ref "R19") (pin "1") (pinfunction "1_1") (pintype "passive"))
      (node (ref "R21") (pin "1") (pinfunction "1_1") (pintype "passive"))
      (node (ref "U3") (pin "4") (pinfunction "IN-_A_4") (pintype "input"))
    )
    (net (code "67") (name "Net-(U5-IN-_A)") (class "Default")
      (node (ref "R20") (pin "1") (pinfunction "1_1") (pintype "passive"))
      (node (ref "R22") (pin "1") (pinfunction "1_1") (pintype "passive"))
      (node (ref "U5") (pin "4") (pinfunction "IN-_A_4") (pintype "input"))
    )
    (net (code "68") (name "Net-(U7-IN-_A)") (class "Default")
      (node (ref "R27") (pin "1") (pinfunction "1_1") (pintype "passive"))
      (node (ref "R29") (pin "1") (pinfunction "1_1") (pintype "passive"))
      (node (ref "U7") (pin "4") (pinfunction "IN-_A_4") (pintype "input"))
    )
    (net (code "69") (name "Net-(U8-IN-_A)") (class "Default")
      (node (ref "R28") (pin "1") (pinfunction "1_1") (pintype "passive"))
      (node (ref "R30") (pin "1") (pinfunction "1_1") (pintype "passive"))
      (node (ref "U8") (pin "4") (pinfunction "IN-_A_4") (pintype "input"))
    )
    (net (code "70") (name "Net-(U9-X1)") (class "Default")
      (node (ref "U9") (pin "1") (pinfunction "X1_1") (pintype "input"))
      (node (ref "Y3") (pin "2") (pinfunction "OSC2_2") (pintype "passive"))
    )
    (net (code "71") (name "Net-(U9-X2)") (class "Default")
      (node (ref "U9") (pin "2") (pinfunction "X2_2") (pintype "output"))
      (node (ref "Y3") (pin "1") (pinfunction "OSC1_1") (pintype "passive"))
    )
    (net (code "72") (name "Net-(Y1-OSC1)") (class "Default")
      (node (ref "C1") (pin "2") (pinfunction "2_2") (pintype "passive"))
      (node (ref "R12") (pin "2") (pinfunction "2_2") (pintype "passive"))
      (node (ref "Y1") (pin "1") (pinfunction "OSC1_1") (pintype "passive"))
    )
    (net (code "73") (name "Net-(Y2-OSC1)") (class "Default")
      (node (ref "C3") (pin "2") (pinfunction "2_2") (pintype "passive"))
      (node (ref "R13") (pin "2") (pinfunction "2_2") (pintype "passive"))
      (node (ref "Y2") (pin "1") (pinfunction "OSC1_1") (pintype "passive"))
    )
    (net (code "74") (name "VBAT_RTC") (class "Default")
      (node (ref "U9") (pin "3") (pinfunction "VBAT_3") (pintype "power_in"))
    )
    (net (code "75") (name "VCAP") (class "Default")
      (node (ref "C10") (pin "2") (pinfunction "2_2") (pintype "passive"))
      (node (ref "U1") (pin "56") (pinfunction "VCAP_56") (pintype "passive"))
    )
    (net (code "76") (name "unconnected-(U1-C2IN1-{slash}PMA2{slash}RPI121{slash}RG9-Pad8)") (class "Default")
      (node (ref "U1") (pin "8") (pinfunction "C2IN1-/PMA2/RPI121/RG9_8") (pintype "passive"))
    )
    (net (code "77") (name "unconnected-(U1-TCK{slash}AN12{slash}PMA11{slash}RPI44{slash}RB12-Pad27)") (class "Default")
      (node (ref "U1") (pin "27") (pinfunction "TCK/AN12/PMA11/RPI44/RB12_27") (pintype "passive"))
    )
    (net (code "78") (name "unconnected-(U1-TDI{slash}AN13{slash}PMA10{slash}RPI45{slash}RB13-Pad28)") (class "Default")
      (node (ref "U1") (pin "28") (pinfunction "TDI/AN13/PMA10/RPI45/RB13_28") (pintype "passive"))
    )
    (net (code "79") (name "unconnected-(U1-TDO{slash}AN11{slash}PMA12{slash}RPI43{slash}RB11-Pad24)") (class "Default")
      (node (ref "U1") (pin "24") (pinfunction "TDO/AN11/PMA12/RPI43/RB11_24") (pintype "passive"))
    )
    (net (code "80") (name "unconnected-(U2-RDY{slash}~{BSY}-Pad5)") (class "Default")
      (node (ref "U2") (pin "5") (pinfunction "RDY/~{BSY}_5") (pintype "open_collector+no_connect"))
    )
    (net (code "81") (name "unconnected-(U4-I1-Pad5)") (class "Default")
      (node (ref "U4") (pin "5") (pinfunction "I1_5") (pintype "passive+no_connect"))
    )
    (net (code "82") (name "unconnected-(U4-I2-Pad4)") (class "Default")
      (node (ref "U4") (pin "4") (pinfunction "I2_4") (pintype "passive+no_connect"))
    )
    (net (code "83") (name "unconnected-(U6-N.C.-Pad4)") (class "Default")
      (node (ref "U6") (pin "4") (pinfunction "N.C._4") (pintype "passive+no_connect"))
    )
    (net (code "84") (name "unconnected-(U6-N.C.-Pad5)") (class "Default")
      (node (ref "U6") (pin "5") (pinfunction "N.C._5") (pintype "passive+no_connect"))
    )
    (net (code "85") (name "unconnected-(U9-SQW{slash}OUT-Pad7)") (class "Default")
      (node (ref "U9") (pin "7") (pinfunction "SQW/OUT_7") (pintype "open_collector+no_connect"))
    )
  )
)
